# Digital.net
KiCad netlist of a schematic drawn in Altium Designer
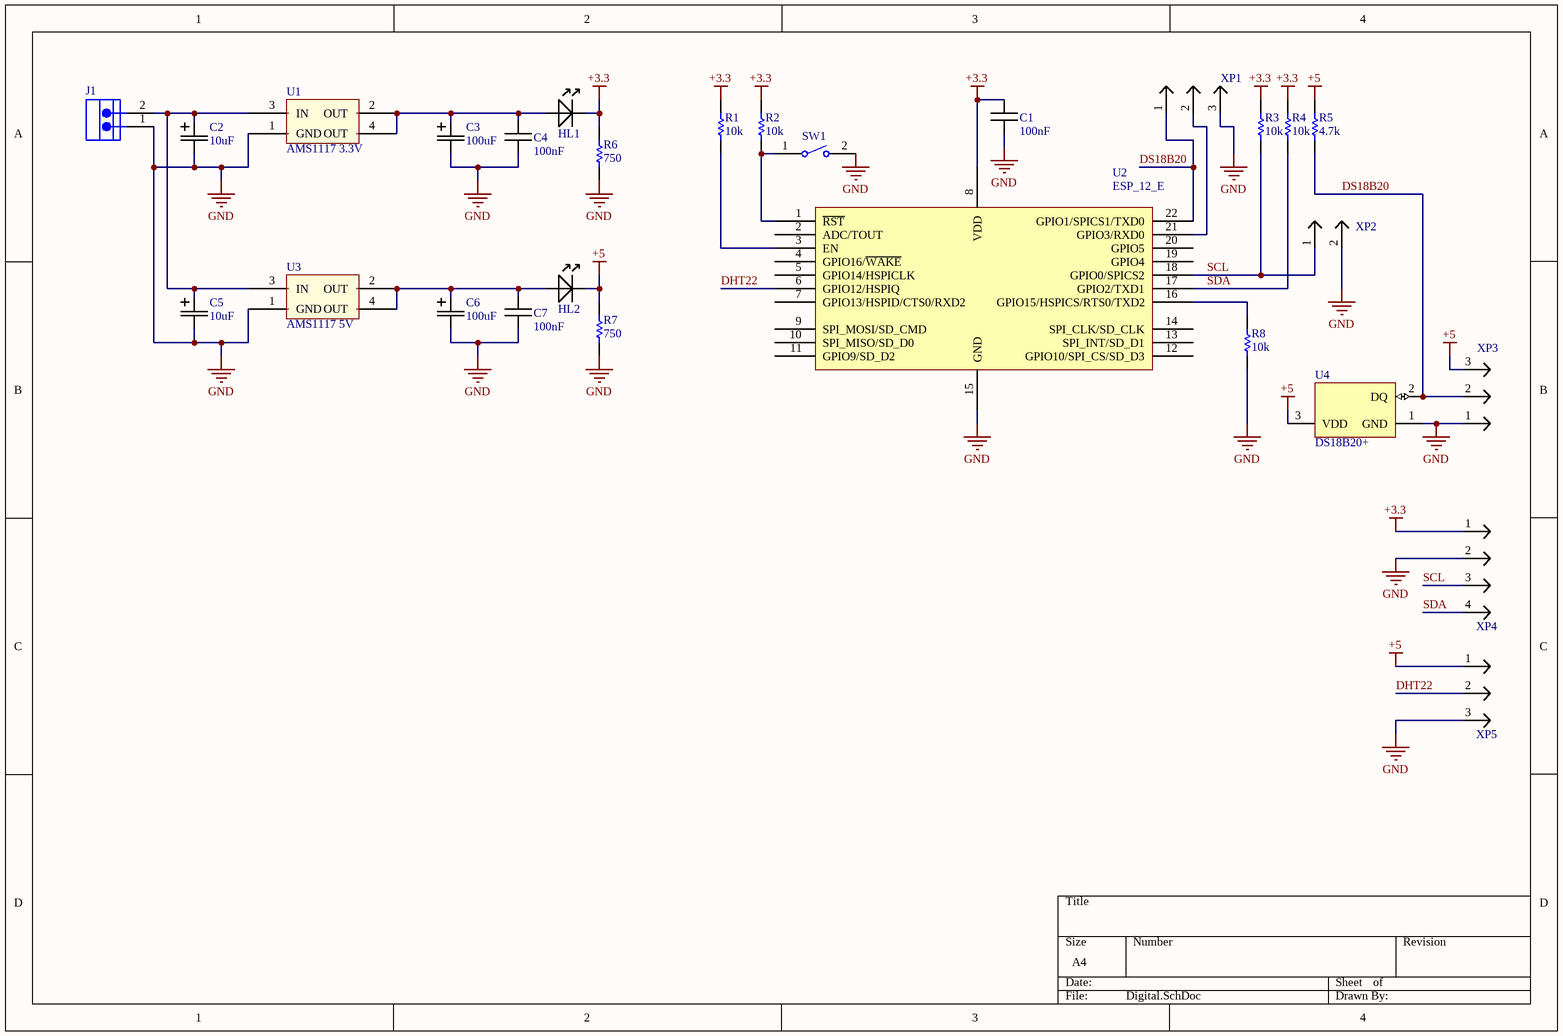
[diagram p0: Digital.SchDoc]

(export (version "E")
  (design (tool "Eeschema 10.0.6"))
  (components
    (comp (ref "C1")
      (value "CAP_SMD")
      (footprint "CAP0805")
      (description "Ceramic capacitor, 0805")
      (fields (field (name "VAL") "100nF"))
      (libsource (lib "altium-import") (part "root_1_CAP_SMD_"))
    )
    (comp (ref "C2")
      (value "CAP_ELEC_5*11")
      (footprint "CAP_ELEC_5*11")
      (description "Electrolitic capacitor")
      (fields (field (name "VAL") "10uF"))
      (libsource (lib "altium-import") (part "root_1_CAP_ELEC_5*11_"))
    )
    (comp (ref "C3")
      (value "CAP_ELEC_8*11")
      (footprint "CAP_ELEC_8*11")
      (description "Electrolitic capacitor")
      (fields (field (name "VAL") "100uF"))
      (libsource (lib "altium-import") (part "root_1_CAP_ELEC_8*11_"))
    )
    (comp (ref "C4")
      (value "CAP_SMD")
      (footprint "CAP0805")
      (description "Ceramic capacitor, 0805")
      (fields (field (name "VAL") "100nF"))
      (libsource (lib "altium-import") (part "root_1_CAP_SMD_"))
    )
    (comp (ref "C5")
      (value "CAP_ELEC_5*11")
      (footprint "CAP_ELEC_5*11")
      (description "Electrolitic capacitor")
      (fields (field (name "VAL") "10uF"))
      (libsource (lib "altium-import") (part "root_1_CAP_ELEC_5*11_"))
    )
    (comp (ref "C6")
      (value "CAP_ELEC_8*11")
      (footprint "CAP_ELEC_8*11")
      (description "Electrolitic capacitor")
      (fields (field (name "VAL") "100uF"))
      (libsource (lib "altium-import") (part "root_1_CAP_ELEC_8*11_"))
    )
    (comp (ref "C7")
      (value "CAP_SMD")
      (footprint "CAP0805")
      (description "Ceramic capacitor, 0805")
      (fields (field (name "VAL") "100nF"))
      (libsource (lib "altium-import") (part "root_1_CAP_SMD_"))
    )
    (comp (ref "HL1")
      (value "LED_SMD")
      (footprint "1206_Led")
      (description "0805 led")
      (libsource (lib "altium-import") (part "root_0_LED_SMD_"))
    )
    (comp (ref "HL2")
      (value "LED_SMD")
      (footprint "1206_Led")
      (description "0805 led")
      (libsource (lib "altium-import") (part "root_0_LED_SMD_"))
    )
    (comp (ref "J1")
      (value "~")
      (footprint "KF350-3.5-02P")
      (fields
        (field (name "MANUFACTURER") "Cixi KaiFeng")
        (field (name "PARTNUMBER") "KF120-02P-14")
        (field (name "CONTACT") "Brass")
      )
      (libsource (lib "altium-import") (part "root_1_Terminal_2_"))
    )
    (comp (ref "R1")
      (value "RES_SMD")
      (footprint "RES0805")
      (fields (field (name "VAL") "10k"))
      (libsource (lib "altium-import") (part "root_1_RES_SMD_"))
    )
    (comp (ref "R2")
      (value "RES_SMD")
      (footprint "RES0805")
      (fields (field (name "VAL") "10k"))
      (libsource (lib "altium-import") (part "root_1_RES_SMD_"))
    )
    (comp (ref "R3")
      (value "RES_SMD")
      (footprint "RES0805")
      (fields (field (name "VAL") "10k"))
      (libsource (lib "altium-import") (part "root_1_RES_SMD_"))
    )
    (comp (ref "R4")
      (value "RES_SMD")
      (footprint "RES0805")
      (fields (field (name "VAL") "10k"))
      (libsource (lib "altium-import") (part "root_1_RES_SMD_"))
    )
    (comp (ref "R5")
      (value "RES_SMD")
      (footprint "RES0805")
      (fields (field (name "VAL") "4.7k"))
      (libsource (lib "altium-import") (part "root_1_RES_SMD_"))
    )
    (comp (ref "R6")
      (value "RES_SMD")
      (footprint "RES0805")
      (fields (field (name "VAL") "750"))
      (libsource (lib "altium-import") (part "root_1_RES_SMD_"))
    )
    (comp (ref "R7")
      (value "RES_SMD")
      (footprint "RES0805")
      (fields (field (name "VAL") "750"))
      (libsource (lib "altium-import") (part "root_1_RES_SMD_"))
    )
    (comp (ref "R8")
      (value "RES_SMD")
      (footprint "RES0805")
      (fields (field (name "VAL") "10k"))
      (libsource (lib "altium-import") (part "root_1_RES_SMD_"))
    )
    (comp (ref "SW1")
      (value "~")
      (footprint "SMD_BUT_6.3mm")
      (fields (field (name "MANUFACTURER") "TE Connectivity"))
      (libsource (lib "altium-import") (part "root_0_Button_2_SMD_"))
    )
    (comp (ref "U1")
      (value "AMS1117 3.3V")
      (footprint "SOT223-4")
      (description "Voltage regulator")
      (libsource (lib "altium-import") (part "root_0_AMS1117_"))
    )
    (comp (ref "U2")
      (value "ESP_12_E")
      (footprint "ESP_12_E")
      (description "ESP-12 Wi-Fi Module by AI-Thinker")
      (libsource (lib "altium-import") (part "root_0_ESP_12_E_"))
    )
    (comp (ref "U3")
      (value "AMS1117 5V")
      (footprint "SOT223-4")
      (description "Voltage regulator")
      (libsource (lib "altium-import") (part "root_0_AMS1117_"))
    )
    (comp (ref "U4")
      (value "DS18B20+")
      (footprint "Q3+1")
      (libsource (lib "altium-import") (part "root_0_DS18B20_"))
    )
    (comp (ref "XP1")
      (value "PLS-03")
      (footprint "PLS-03")
      (libsource (lib "altium-import") (part "root_1_PLS-03_"))
    )
    (comp (ref "XP2")
      (value "PLS-02")
      (footprint "PLS-02")
      (libsource (lib "altium-import") (part "root_1_PLS-02_"))
    )
    (comp (ref "XP3")
      (value "PLS-03")
      (footprint "PLS-03")
      (libsource (lib "altium-import") (part "root_2_mirrored_PLS-03_"))
    )
    (comp (ref "XP4")
      (value "PBS-04")
      (footprint "PBS-04")
      (libsource (lib "altium-import") (part "root_0_PBS-04_"))
    )
    (comp (ref "XP5")
      (value "PBS-03")
      (footprint "PBS-03")
      (libsource (lib "altium-import") (part "root_0_PBS-03_"))
    )
  )
  (nets
    (net (code "1") (name "+3.3") (class "Default")
      (node (ref "C1") (pin "2") (pinfunction "2_2") (pintype "passive"))
      (node (ref "HL1") (pin "2") (pinfunction "cathode_2") (pintype "passive"))
      (node (ref "R1") (pin "2") (pinfunction "2_2") (pintype "passive"))
      (node (ref "R2") (pin "2") (pinfunction "2_2") (pintype "passive"))
      (node (ref "R3") (pin "2") (pinfunction "2_2") (pintype "passive"))
      (node (ref "R4") (pin "2") (pinfunction "2_2") (pintype "passive"))
      (node (ref "R6") (pin "2") (pinfunction "2_2") (pintype "passive"))
      (node (ref "U2") (pin "8") (pinfunction "VDD_8") (pintype "passive"))
      (node (ref "XP4") (pin "1") (pinfunction "1_1") (pintype "passive"))
    )
    (net (code "2") (name "+5") (class "Default")
      (node (ref "HL2") (pin "2") (pinfunction "cathode_2") (pintype "passive"))
      (node (ref "R5") (pin "2") (pinfunction "2_2") (pintype "passive"))
      (node (ref "R7") (pin "2") (pinfunction "2_2") (pintype "passive"))
      (node (ref "U4") (pin "3") (pinfunction "VDD_3") (pintype "power_in"))
      (node (ref "XP3") (pin "3") (pinfunction "3_3") (pintype "passive"))
      (node (ref "XP5") (pin "1") (pinfunction "1_1") (pintype "passive"))
    )
    (net (code "3") (name "/DHT22") (class "Default")
      (node (ref "U2") (pin "6") (pinfunction "GPIO12/HSPIQ_6") (pintype "passive"))
      (node (ref "XP5") (pin "2") (pinfunction "2_2") (pintype "passive"))
    )
    (net (code "4") (name "/DS18B20") (class "Default")
      (node (ref "R5") (pin "1") (pinfunction "1_1") (pintype "passive"))
      (node (ref "U2") (pin "22") (pinfunction "GPIO1/SPICS1/TXD0_22") (pintype "passive"))
      (node (ref "U4") (pin "2") (pinfunction "DQ_2") (pintype "bidirectional"))
      (node (ref "XP1") (pin "1") (pinfunction "1_1") (pintype "passive"))
      (node (ref "XP3") (pin "2") (pinfunction "2_2") (pintype "passive"))
    )
    (net (code "5") (name "/SCL") (class "Default")
      (node (ref "R3") (pin "1") (pinfunction "1_1") (pintype "passive"))
      (node (ref "U2") (pin "18") (pinfunction "GPIO0/SPICS2_18") (pintype "passive"))
      (node (ref "XP2") (pin "1") (pinfunction "1_1") (pintype "passive"))
      (node (ref "XP4") (pin "3") (pinfunction "3_3") (pintype "passive"))
    )
    (net (code "6") (name "/SDA") (class "Default")
      (node (ref "R4") (pin "1") (pinfunction "1_1") (pintype "passive"))
      (node (ref "U2") (pin "17") (pinfunction "GPIO2/TXD1_17") (pintype "passive"))
      (node (ref "XP4") (pin "4") (pinfunction "4_4") (pintype "passive"))
    )
    (net (code "7") (name "GND") (class "Default")
      (node (ref "C1") (pin "1") (pinfunction "1_1") (pintype "passive"))
      (node (ref "C2") (pin "1") (pinfunction "1_1") (pintype "passive"))
      (node (ref "C3") (pin "1") (pinfunction "1_1") (pintype "passive"))
      (node (ref "C4") (pin "1") (pinfunction "1_1") (pintype "passive"))
      (node (ref "C5") (pin "1") (pinfunction "1_1") (pintype "passive"))
      (node (ref "C6") (pin "1") (pinfunction "1_1") (pintype "passive"))
      (node (ref "C7") (pin "1") (pinfunction "1_1") (pintype "passive"))
      (node (ref "J1") (pin "1") (pinfunction "1_1") (pintype "passive"))
      (node (ref "R6") (pin "1") (pinfunction "1_1") (pintype "passive"))
      (node (ref "R7") (pin "1") (pinfunction "1_1") (pintype "passive"))
      (node (ref "R8") (pin "1") (pinfunction "1_1") (pintype "passive"))
      (node (ref "SW1") (pin "2") (pinfunction "2_2") (pintype "passive"))
      (node (ref "U1") (pin "1") (pinfunction "GND_1") (pintype "passive"))
      (node (ref "U2") (pin "15") (pinfunction "GND_15") (pintype "passive"))
      (node (ref "U3") (pin "1") (pinfunction "GND_1") (pintype "passive"))
      (node (ref "U4") (pin "1") (pinfunction "GND_1") (pintype "power_in"))
      (node (ref "XP1") (pin "3") (pinfunction "3_3") (pintype "passive"))
      (node (ref "XP2") (pin "2") (pinfunction "2_2") (pintype "passive"))
      (node (ref "XP3") (pin "1") (pinfunction "1_1") (pintype "passive"))
      (node (ref "XP4") (pin "2") (pinfunction "2_2") (pintype "passive"))
      (node (ref "XP5") (pin "3") (pinfunction "3_3") (pintype "passive"))
    )
    (net (code "8") (name "Net-(HL1-anode)") (class "Default")
      (node (ref "C3") (pin "2") (pinfunction "2_2") (pintype "passive"))
      (node (ref "C4") (pin "2") (pinfunction "2_2") (pintype "passive"))
      (node (ref "HL1") (pin "1") (pinfunction "anode_1") (pintype "passive"))
      (node (ref "U1") (pin "2") (pinfunction "OUT_2") (pintype "passive"))
      (node (ref "U1") (pin "4") (pinfunction "OUT_4") (pintype "passive"))
    )
    (net (code "9") (name "Net-(HL2-anode)") (class "Default")
      (node (ref "C6") (pin "2") (pinfunction "2_2") (pintype "passive"))
      (node (ref "C7") (pin "2") (pinfunction "2_2") (pintype "passive"))
      (node (ref "HL2") (pin "1") (pinfunction "anode_1") (pintype "passive"))
      (node (ref "U3") (pin "2") (pinfunction "OUT_2") (pintype "passive"))
      (node (ref "U3") (pin "4") (pinfunction "OUT_4") (pintype "passive"))
    )
    (net (code "10") (name "Net-(U1-IN)") (class "Default")
      (node (ref "C2") (pin "2") (pinfunction "2_2") (pintype "passive"))
      (node (ref "C5") (pin "2") (pinfunction "2_2") (pintype "passive"))
      (node (ref "J1") (pin "2") (pinfunction "2_2") (pintype "passive"))
      (node (ref "U1") (pin "3") (pinfunction "IN_3") (pintype "passive"))
      (node (ref "U3") (pin "3") (pinfunction "IN_3") (pintype "passive"))
    )
    (net (code "11") (name "Net-(U2-EN)") (class "Default")
      (node (ref "R1") (pin "1") (pinfunction "1_1") (pintype "passive"))
      (node (ref "U2") (pin "3") (pinfunction "EN_3") (pintype "passive"))
    )
    (net (code "12") (name "Net-(U2-GPIO3{slash}RXD0)") (class "Default")
      (node (ref "U2") (pin "21") (pinfunction "GPIO3/RXD0_21") (pintype "passive"))
      (node (ref "XP1") (pin "2") (pinfunction "2_2") (pintype "passive"))
    )
    (net (code "13") (name "Net-(U2-GPIO15{slash}HSPICS{slash}RTS0{slash}TXD2)") (class "Default")
      (node (ref "R8") (pin "2") (pinfunction "2_2") (pintype "passive"))
      (node (ref "U2") (pin "16") (pinfunction "GPIO15/HSPICS/RTS0/TXD2_16") (pintype "passive"))
    )
    (net (code "14") (name "Net-(U2-~{RST})") (class "Default")
      (node (ref "R2") (pin "1") (pinfunction "1_1") (pintype "passive"))
      (node (ref "SW1") (pin "1") (pinfunction "1_1") (pintype "passive"))
      (node (ref "U2") (pin "1") (pinfunction "~{RST}_1") (pintype "passive"))
    )
    (net (code "15") (name "unconnected-(U2-ADC{slash}TOUT-Pad2)") (class "Default")
      (node (ref "U2") (pin "2") (pinfunction "ADC/TOUT_2") (pintype "passive"))
    )
    (net (code "16") (name "unconnected-(U2-GPIO4-Pad19)") (class "Default")
      (node (ref "U2") (pin "19") (pinfunction "GPIO4_19") (pintype "passive"))
    )
    (net (code "17") (name "unconnected-(U2-GPIO5-Pad20)") (class "Default")
      (node (ref "U2") (pin "20") (pinfunction "GPIO5_20") (pintype "passive"))
    )
    (net (code "18") (name "unconnected-(U2-GPIO9{slash}SD_D2-Pad11)") (class "Default")
      (node (ref "U2") (pin "11") (pinfunction "GPIO9/SD_D2_11") (pintype "passive"))
    )
    (net (code "19") (name "unconnected-(U2-GPIO10{slash}SPI_CS{slash}SD_D3-Pad12)") (class "Default")
      (node (ref "U2") (pin "12") (pinfunction "GPIO10/SPI_CS/SD_D3_12") (pintype "passive"))
    )
    (net (code "20") (name "unconnected-(U2-GPIO13{slash}HSPID{slash}CTS0{slash}RXD2-Pad7)") (class "Default")
      (node (ref "U2") (pin "7") (pinfunction "GPIO13/HSPID/CTS0/RXD2_7") (pintype "passive"))
    )
    (net (code "21") (name "unconnected-(U2-GPIO14{slash}HSPICLK-Pad5)") (class "Default")
      (node (ref "U2") (pin "5") (pinfunction "GPIO14/HSPICLK_5") (pintype "passive"))
    )
    (net (code "22") (name "unconnected-(U2-GPIO16{slash}~{WAKE}-Pad4)") (class "Default")
      (node (ref "U2") (pin "4") (pinfunction "GPIO16/~{WAKE}_4") (pintype "passive"))
    )
    (net (code "23") (name "unconnected-(U2-SPI_CLK{slash}SD_CLK-Pad14)") (class "Default")
      (node (ref "U2") (pin "14") (pinfunction "SPI_CLK/SD_CLK_14") (pintype "passive"))
    )
    (net (code "24") (name "unconnected-(U2-SPI_INT{slash}SD_D1-Pad13)") (class "Default")
      (node (ref "U2") (pin "13") (pinfunction "SPI_INT/SD_D1_13") (pintype "passive"))
    )
    (net (code "25") (name "unconnected-(U2-SPI_MISO{slash}SD_D0-Pad10)") (class "Default")
      (node (ref "U2") (pin "10") (pinfunction "SPI_MISO/SD_D0_10") (pintype "passive"))
    )
    (net (code "26") (name "unconnected-(U2-SPI_MOSI{slash}SD_CMD-Pad9)") (class "Default")
      (node (ref "U2") (pin "9") (pinfunction "SPI_MOSI/SD_CMD_9") (pintype "passive"))
    )
  )
)
